# 555.net
KiCad netlist of a schematic drawn in EAGLE
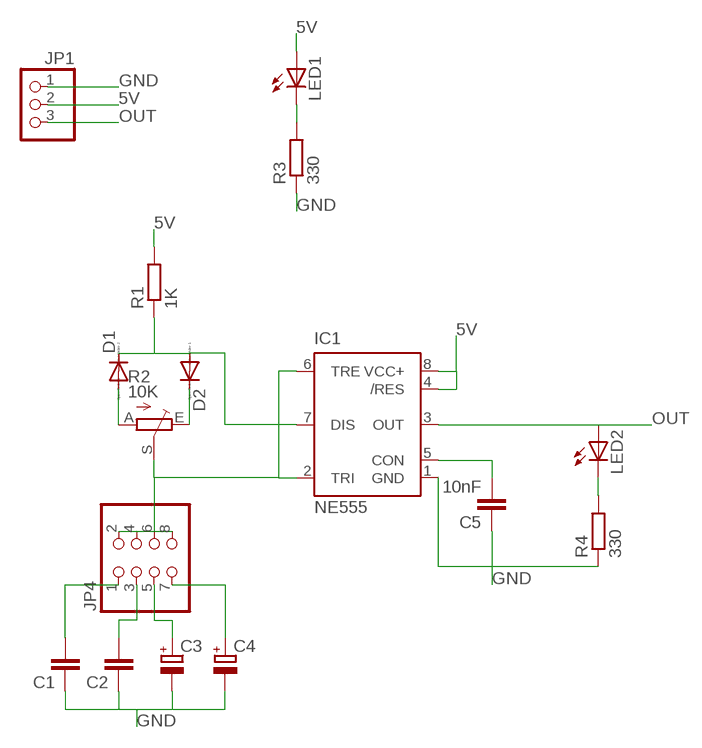
[diagram p0: schematic, sheet 1]

(export (version "E")
  (design (tool "Eeschema 10.0.6"))
  (components
    (comp (ref "C1")
      (value "C-EU025-030X050")
      (footprint "eagle-import:C025-030X050")
      (libsource (lib "eagle-import") (part "C-EU025-030X050"))
    )
    (comp (ref "C2")
      (value "C-EU025-030X050")
      (footprint "eagle-import:C025-030X050")
      (libsource (lib "eagle-import") (part "C-EU025-030X050"))
    )
    (comp (ref "C3")
      (value "CPOL-EUE2.5-6")
      (footprint "eagle-import:E2,5-6")
      (libsource (lib "eagle-import") (part "CPOL-EUE2.5-6"))
    )
    (comp (ref "C4")
      (value "CPOL-EUE2.5-6")
      (footprint "eagle-import:E2,5-6")
      (libsource (lib "eagle-import") (part "CPOL-EUE2.5-6"))
    )
    (comp (ref "C5")
      (value "10nF")
      (footprint "eagle-import:C025-030X050")
      (libsource (lib "eagle-import") (part "C-EU025-030X050"))
    )
    (comp (ref "D1")
      (value "1N4148DO35-7")
      (footprint "eagle-import:DO35-7")
      (libsource (lib "eagle-import") (part "1N4148DO35-7"))
    )
    (comp (ref "D2")
      (value "1N4148DO35-7")
      (footprint "eagle-import:DO35-7")
      (libsource (lib "eagle-import") (part "1N4148DO35-7"))
    )
    (comp (ref "IC1")
      (value "NE555")
      (footprint "eagle-import:DIL-08")
      (fields (field (name "MF") "Arrow Electronics") (field (name "MPN") "NE555N"))
      (libsource (lib "eagle-import") (part "NE555"))
    )
    (comp (ref "JP1")
      (value "PINHD-1X3")
      (footprint "eagle-import:1X03")
      (libsource (lib "eagle-import") (part "PINHD-1X3"))
    )
    (comp (ref "JP4")
      (value "PINHD-2X4")
      (footprint "eagle-import:2X04")
      (libsource (lib "eagle-import") (part "PINHD-2X4"))
    )
    (comp (ref "LED1")
      (value "LED3MM")
      (footprint "eagle-import:LED3MM")
      (libsource (lib "eagle-import") (part "LED3MM"))
    )
    (comp (ref "LED2")
      (value "LED3MM")
      (footprint "eagle-import:LED3MM")
      (libsource (lib "eagle-import") (part "LED3MM"))
    )
    (comp (ref "R1")
      (value "1K")
      (footprint "eagle-import:0207_7")
      (libsource (lib "eagle-import") (part "R-EU_0207/7"))
    )
    (comp (ref "R2")
      (value "10K")
      (footprint "eagle-import:CA6V")
      (libsource (lib "eagle-import") (part "TRIM_EU-CA6V"))
    )
    (comp (ref "R3")
      (value "330")
      (footprint "eagle-import:0207_7")
      (libsource (lib "eagle-import") (part "R-EU_0207/7"))
    )
    (comp (ref "R4")
      (value "330")
      (footprint "eagle-import:0207_7")
      (libsource (lib "eagle-import") (part "R-EU_0207/7"))
    )
  )
  (nets
    (net (code "1") (name "/5V") (class "Default")
      (node (ref "IC1") (pin "4") (pinfunction "/RES_4") (pintype "input"))
      (node (ref "IC1") (pin "8") (pinfunction "VCC+_8") (pintype "power_in"))
      (node (ref "JP1") (pin "2") (pinfunction "2_2") (pintype "passive"))
      (node (ref "LED1") (pin "A") (pinfunction "A_A") (pintype "passive"))
      (node (ref "R1") (pin "2") (pinfunction "2_2") (pintype "passive"))
    )
    (net (code "2") (name "/GND") (class "Default")
      (node (ref "C1") (pin "1") (pinfunction "1_1") (pintype "passive"))
      (node (ref "C2") (pin "1") (pinfunction "1_1") (pintype "passive"))
      (node (ref "C3") (pin "-") (pinfunction "-_-") (pintype "passive"))
      (node (ref "C4") (pin "-") (pinfunction "-_-") (pintype "passive"))
      (node (ref "C5") (pin "1") (pinfunction "1_1") (pintype "passive"))
      (node (ref "IC1") (pin "1") (pinfunction "GND_1") (pintype "power_in"))
      (node (ref "JP1") (pin "1") (pinfunction "1_1") (pintype "passive"))
      (node (ref "R3") (pin "1") (pinfunction "1_1") (pintype "passive"))
      (node (ref "R4") (pin "1") (pinfunction "1_1") (pintype "passive"))
    )
    (net (code "3") (name "/OUT") (class "Default")
      (node (ref "IC1") (pin "3") (pinfunction "OUT_3") (pintype "output"))
      (node (ref "JP1") (pin "3") (pinfunction "3_3") (pintype "passive"))
      (node (ref "LED2") (pin "A") (pinfunction "A_A") (pintype "passive"))
    )
    (net (code "4") (name "Net-(C1-Pad2)") (class "Default")
      (node (ref "C1") (pin "2") (pinfunction "2_2") (pintype "passive"))
      (node (ref "JP4") (pin "1") (pinfunction "1_1") (pintype "passive"))
    )
    (net (code "5") (name "Net-(C2-Pad2)") (class "Default")
      (node (ref "C2") (pin "2") (pinfunction "2_2") (pintype "passive"))
      (node (ref "JP4") (pin "3") (pinfunction "3_3") (pintype "passive"))
    )
    (net (code "6") (name "Net-(C3-Pad+)") (class "Default")
      (node (ref "C3") (pin "+") (pinfunction "+_+") (pintype "passive"))
      (node (ref "JP4") (pin "5") (pinfunction "5_5") (pintype "passive"))
    )
    (net (code "7") (name "Net-(C4-Pad+)") (class "Default")
      (node (ref "C4") (pin "+") (pinfunction "+_+") (pintype "passive"))
      (node (ref "JP4") (pin "7") (pinfunction "7_7") (pintype "passive"))
    )
    (net (code "8") (name "Net-(D1-PadA)") (class "Default")
      (node (ref "D1") (pin "A") (pinfunction "A_A") (pintype "passive"))
      (node (ref "R2") (pin "A") (pinfunction "A_A") (pintype "passive"))
    )
    (net (code "9") (name "Net-(D2-PadC)") (class "Default")
      (node (ref "D2") (pin "C") (pinfunction "C_C") (pintype "passive"))
      (node (ref "R2") (pin "E") (pinfunction "E_E") (pintype "passive"))
    )
    (net (code "10") (name "Net-(IC1-CON)") (class "Default")
      (node (ref "C5") (pin "2") (pinfunction "2_2") (pintype "passive"))
      (node (ref "IC1") (pin "5") (pinfunction "CON_5") (pintype "input"))
    )
    (net (code "11") (name "Net-(IC1-DIS)") (class "Default")
      (node (ref "D1") (pin "C") (pinfunction "C_C") (pintype "passive"))
      (node (ref "D2") (pin "A") (pinfunction "A_A") (pintype "passive"))
      (node (ref "IC1") (pin "7") (pinfunction "DIS_7") (pintype "input"))
      (node (ref "R1") (pin "1") (pinfunction "1_1") (pintype "passive"))
    )
    (net (code "12") (name "Net-(IC1-TRE)") (class "Default")
      (node (ref "IC1") (pin "2") (pinfunction "TRI_2") (pintype "input"))
      (node (ref "IC1") (pin "6") (pinfunction "TRE_6") (pintype "input"))
      (node (ref "JP4") (pin "2") (pinfunction "2_2") (pintype "passive"))
      (node (ref "JP4") (pin "4") (pinfunction "4_4") (pintype "passive"))
      (node (ref "JP4") (pin "6") (pinfunction "6_6") (pintype "passive"))
      (node (ref "JP4") (pin "8") (pinfunction "8_8") (pintype "passive"))
      (node (ref "R2") (pin "S") (pinfunction "S_S") (pintype "passive"))
    )
    (net (code "13") (name "Net-(LED1-C)") (class "Default")
      (node (ref "LED1") (pin "K") (pinfunction "C_K") (pintype "passive"))
      (node (ref "R3") (pin "2") (pinfunction "2_2") (pintype "passive"))
    )
    (net (code "14") (name "Net-(LED2-C)") (class "Default")
      (node (ref "LED2") (pin "K") (pinfunction "C_K") (pintype "passive"))
      (node (ref "R4") (pin "2") (pinfunction "2_2") (pintype "passive"))
    )
  )
)
